# CTRL.net
KiCad netlist of a schematic drawn in EAGLE
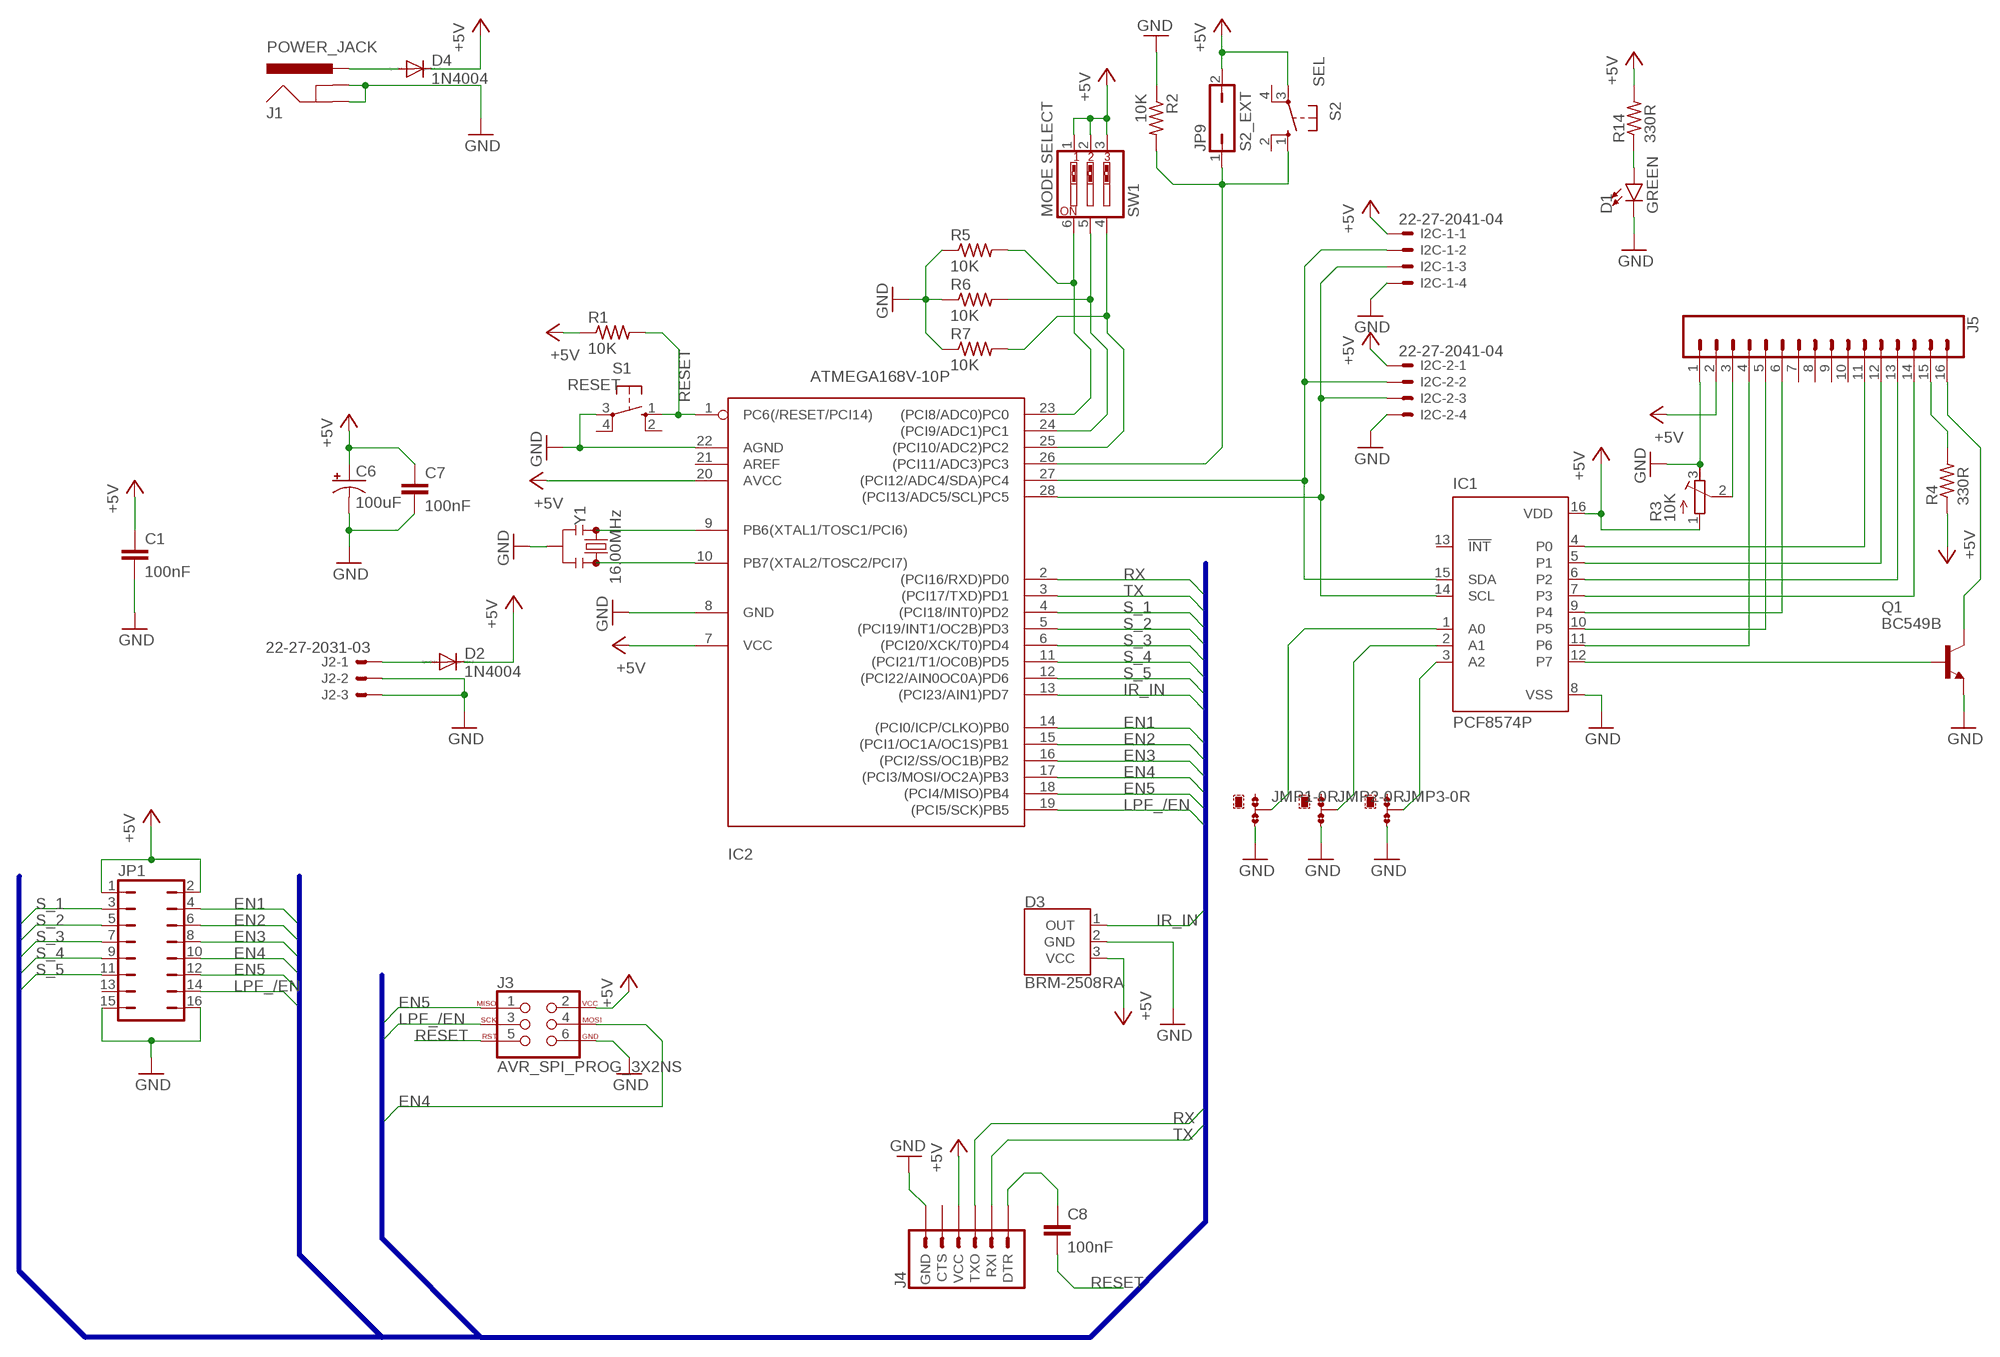
[diagram p0: schematic, sheet 1]

(export (version "E")
  (design (tool "Eeschema 10.0.6"))
  (components
    (comp (ref "C1")
      (value "100nF")
      (footprint "eagle-import:C075-032X103")
      (libsource (lib "eagle-import") (part "C-EU075-032X103"))
    )
    (comp (ref "C6")
      (value "100uF")
      (footprint "eagle-import:E2,5-7")
      (libsource (lib "eagle-import") (part "CPOL-USE2.5-7"))
    )
    (comp (ref "C7")
      (value "100nF")
      (footprint "eagle-import:C075-032X103")
      (libsource (lib "eagle-import") (part "C-EU075-032X103"))
    )
    (comp (ref "C8")
      (value "100nF")
      (footprint "eagle-import:C075-032X103")
      (libsource (lib "eagle-import") (part "C-EU075-032X103"))
    )
    (comp (ref "D1")
      (value "GREEN")
      (footprint "eagle-import:LED_5MM")
      (libsource (lib "eagle-import") (part "LED5MM"))
    )
    (comp (ref "D2")
      (value "1N4004")
      (footprint "eagle-import:DO41-10")
      (libsource (lib "eagle-import") (part "1N4004"))
    )
    (comp (ref "D3")
      (value "BRM-2508RA")
      (footprint "eagle-import:BRM-2508")
      (libsource (lib "eagle-import") (part "BRM-2508RA"))
    )
    (comp (ref "D4")
      (value "1N4004")
      (footprint "eagle-import:DO41-10")
      (libsource (lib "eagle-import") (part "1N4004"))
    )
    (comp (ref "I2C-1")
      (value "22-27-2041-04")
      (footprint "eagle-import:6410-04")
      (libsource (lib "eagle-import") (part "22-?-0427-2041"))
    )
    (comp (ref "I2C-2")
      (value "22-27-2041-04")
      (footprint "eagle-import:6410-04")
      (libsource (lib "eagle-import") (part "22-?-0427-2041"))
    )
    (comp (ref "IC1")
      (value "PCF8574P")
      (footprint "eagle-import:DIL16")
      (fields (field (name "MPN") "PCF8574PN"))
      (libsource (lib "eagle-import") (part "PCF8574P"))
    )
    (comp (ref "IC2")
      (value "ATMEGA168V-10P")
      (footprint "eagle-import:DIL28-3")
      (libsource (lib "eagle-import") (part "ATMEGA168PV-10"))
    )
    (comp (ref "J1")
      (value "POWER_JACK")
      (footprint "eagle-import:POWER_JACK_PTH")
      (libsource (lib "eagle-import") (part "POWER_JACK"))
    )
    (comp (ref "J2")
      (value "22-27-2031-03")
      (footprint "eagle-import:6410-03")
      (libsource (lib "eagle-import") (part "22-?-0327-2031"))
    )
    (comp (ref "J3")
      (value "AVR_SPI_PROG_3X2NS")
      (footprint "eagle-import:2X3-NS")
      (libsource (lib "eagle-import") (part "AVR_SPI_PROG_3X2NS"))
    )
    (comp (ref "J4")
      (value "6_PIN_SERIAL_TARGETSILK")
      (footprint "eagle-import:6_PIN_SERIAL_TARGET_SIDE_W_SILK")
      (libsource (lib "eagle-import") (part "6_PIN_SERIAL_TARGETSILK"))
    )
    (comp (ref "J5")
      (value "CONN_16LONGPADS")
      (footprint "eagle-import:1X16_LONGPADS")
      (libsource (lib "eagle-import") (part "CONN_16LONGPADS"))
    )
    (comp (ref "JMP1")
      (value "0R-JUMPB")
      (footprint "eagle-import:B0R-JMP")
      (libsource (lib "eagle-import") (part "0R-JUMPB"))
    )
    (comp (ref "JMP2")
      (value "0R-JUMPB")
      (footprint "eagle-import:B0R-JMP")
      (libsource (lib "eagle-import") (part "0R-JUMPB"))
    )
    (comp (ref "JMP3")
      (value "0R-JUMPB")
      (footprint "eagle-import:B0R-JMP")
      (libsource (lib "eagle-import") (part "0R-JUMPB"))
    )
    (comp (ref "JP1")
      (value "JP8Q")
      (footprint "eagle-import:JP8Q")
      (libsource (lib "eagle-import") (part "JP8Q"))
    )
    (comp (ref "JP9")
      (value "S2_EXT")
      (footprint "eagle-import:JP1")
      (libsource (lib "eagle-import") (part "JP1Q"))
    )
    (comp (ref "Q1")
      (value "BC549B")
      (footprint "eagle-import:TO92-EBC")
      (libsource (lib "eagle-import") (part "BC549B"))
    )
    (comp (ref "R1")
      (value "10K")
      (footprint "eagle-import:0204_7")
      (libsource (lib "eagle-import") (part "R-US_0204/7"))
    )
    (comp (ref "R2")
      (value "10K")
      (footprint "eagle-import:0204_7")
      (libsource (lib "eagle-import") (part "R-US_0204/7"))
    )
    (comp (ref "R3")
      (value "10K")
      (footprint "eagle-import:RTRIM3296P")
      (libsource (lib "eagle-import") (part "R-TRIMM3296P"))
    )
    (comp (ref "R4")
      (value "330R")
      (footprint "eagle-import:0204_7")
      (libsource (lib "eagle-import") (part "resistor_R-US_0204/7"))
    )
    (comp (ref "R5")
      (value "10K")
      (footprint "eagle-import:0204_7")
      (libsource (lib "eagle-import") (part "R-US_0204/7"))
    )
    (comp (ref "R6")
      (value "10K")
      (footprint "eagle-import:0204_7")
      (libsource (lib "eagle-import") (part "R-US_0204/7"))
    )
    (comp (ref "R7")
      (value "10K")
      (footprint "eagle-import:0204_7")
      (libsource (lib "eagle-import") (part "R-US_0204/7"))
    )
    (comp (ref "R14")
      (value "330R")
      (footprint "eagle-import:0204_7")
      (libsource (lib "eagle-import") (part "resistor_R-US_0204/7"))
    )
    (comp (ref "S1")
      (value "RESET")
      (footprint "eagle-import:B3F-10XX")
      (fields (field (name "MPN") "B3F-1000"))
      (libsource (lib "eagle-import") (part "10-XX"))
    )
    (comp (ref "S2")
      (value "SEL")
      (footprint "eagle-import:B3F-10XX")
      (fields (field (name "MPN") "B3F-1000"))
      (libsource (lib "eagle-import") (part "10-XX"))
    )
    (comp (ref "SW1")
      (value "MODE SELECT")
      (footprint "eagle-import:EDG-03")
      (libsource (lib "eagle-import") (part "SW_DIP-3"))
    )
    (comp (ref "Y1")
      (value "16.00MHz")
      (footprint "eagle-import:RESONATOR-PTH-7.6X3.8")
      (libsource (lib "eagle-import") (part "RESONATORPTH-7.6X3.8"))
    )
  )
  (nets
    (net (code "1") (name "+5V") (class "Default")
      (node (ref "C1") (pin "1") (pinfunction "1_1") (pintype "passive"))
      (node (ref "C6") (pin "+") (pinfunction "+_+") (pintype "passive"))
      (node (ref "C7") (pin "1") (pinfunction "1_1") (pintype "passive"))
      (node (ref "D2") (pin "C") (pinfunction "C_C") (pintype "passive"))
      (node (ref "D3") (pin "3") (pinfunction "VCC_3") (pintype "bidirectional"))
      (node (ref "D4") (pin "C") (pinfunction "C_C") (pintype "passive"))
      (node (ref "I2C-1") (pin "1") (pinfunction "S_1") (pintype "passive"))
      (node (ref "I2C-2") (pin "1") (pinfunction "S_1") (pintype "passive"))
      (node (ref "IC1") (pin "16") (pinfunction "VDD_16") (pintype "power_in"))
      (node (ref "IC2") (pin "20") (pinfunction "AVCC_20") (pintype "bidirectional"))
      (node (ref "IC2") (pin "7") (pinfunction "VCC_7") (pintype "bidirectional"))
      (node (ref "J3") (pin "2") (pinfunction "2_2") (pintype "passive"))
      (node (ref "J4") (pin "P$4") (pinfunction "VCC_P$4") (pintype "passive"))
      (node (ref "J5") (pin "2") (pinfunction "2_2") (pintype "passive"))
      (node (ref "JP1") (pin "1") (pinfunction "1_1") (pintype "passive"))
      (node (ref "JP1") (pin "2") (pinfunction "2_2") (pintype "passive"))
      (node (ref "JP9") (pin "2") (pinfunction "2_2") (pintype "passive"))
      (node (ref "R1") (pin "1") (pinfunction "1_1") (pintype "passive"))
      (node (ref "R14") (pin "2") (pinfunction "2_2") (pintype "passive"))
      (node (ref "R3") (pin "1") (pinfunction "A_1") (pintype "passive"))
      (node (ref "R4") (pin "1") (pinfunction "1_1") (pintype "passive"))
      (node (ref "S2") (pin "3") (pinfunction "P_3") (pintype "passive"))
      (node (ref "SW1") (pin "1") (pinfunction "1_1") (pintype "passive"))
      (node (ref "SW1") (pin "2") (pinfunction "2_2") (pintype "passive"))
      (node (ref "SW1") (pin "3") (pinfunction "3_3") (pintype "passive"))
    )
    (net (code "2") (name "/EN1") (class "Default")
      (node (ref "IC2") (pin "14") (pinfunction "(PCI0/ICP/CLKO)PB0_14") (pintype "bidirectional"))
      (node (ref "JP1") (pin "4") (pinfunction "4_4") (pintype "passive"))
    )
    (net (code "3") (name "/EN2") (class "Default")
      (node (ref "IC2") (pin "15") (pinfunction "(PCI1/OC1A/OC1S)PB1_15") (pintype "bidirectional"))
      (node (ref "JP1") (pin "6") (pinfunction "6_6") (pintype "passive"))
    )
    (net (code "4") (name "/EN3") (class "Default")
      (node (ref "IC2") (pin "16") (pinfunction "(PCI2/SS/OC1B)PB2_16") (pintype "bidirectional"))
      (node (ref "JP1") (pin "8") (pinfunction "8_8") (pintype "passive"))
    )
    (net (code "5") (name "/EN4") (class "Default")
      (node (ref "IC2") (pin "17") (pinfunction "(PCI3/MOSI/OC2A)PB3_17") (pintype "bidirectional"))
      (node (ref "J3") (pin "4") (pinfunction "4_4") (pintype "passive"))
      (node (ref "JP1") (pin "10") (pinfunction "10_10") (pintype "passive"))
    )
    (net (code "6") (name "/EN5") (class "Default")
      (node (ref "IC2") (pin "18") (pinfunction "(PCI4/MISO)PB4_18") (pintype "bidirectional"))
      (node (ref "J3") (pin "1") (pinfunction "1_1") (pintype "passive"))
      (node (ref "JP1") (pin "12") (pinfunction "12_12") (pintype "passive"))
    )
    (net (code "7") (name "/IR_IN") (class "Default")
      (node (ref "D3") (pin "1") (pinfunction "OUT_1") (pintype "bidirectional"))
      (node (ref "IC2") (pin "13") (pinfunction "(PCI23/AIN1)PD7_13") (pintype "bidirectional"))
    )
    (net (code "8") (name "/LPF_{slash}EN") (class "Default")
      (node (ref "IC2") (pin "19") (pinfunction "(PCI5/SCK)PB5_19") (pintype "bidirectional"))
      (node (ref "J3") (pin "3") (pinfunction "3_3") (pintype "passive"))
      (node (ref "JP1") (pin "14") (pinfunction "14_14") (pintype "passive"))
    )
    (net (code "9") (name "/RESET") (class "Default")
      (node (ref "C8") (pin "2") (pinfunction "2_2") (pintype "passive"))
      (node (ref "IC2") (pin "1") (pinfunction "PC6(/RESET/PCI14)_1") (pintype "bidirectional"))
      (node (ref "J3") (pin "5") (pinfunction "5_5") (pintype "passive"))
      (node (ref "R1") (pin "2") (pinfunction "2_2") (pintype "passive"))
      (node (ref "S1") (pin "1") (pinfunction "S_1") (pintype "passive"))
    )
    (net (code "10") (name "/RX") (class "Default")
      (node (ref "IC2") (pin "2") (pinfunction "(PCI16/RXD)PD0_2") (pintype "bidirectional"))
      (node (ref "J4") (pin "P$2") (pinfunction "TXO_P$2") (pintype "passive"))
    )
    (net (code "11") (name "/S_1") (class "Default")
      (node (ref "IC2") (pin "4") (pinfunction "(PCI18/INT0)PD2_4") (pintype "bidirectional"))
      (node (ref "JP1") (pin "3") (pinfunction "3_3") (pintype "passive"))
    )
    (net (code "12") (name "/S_2") (class "Default")
      (node (ref "IC2") (pin "5") (pinfunction "(PCI19/INT1/OC2B)PD3_5") (pintype "bidirectional"))
      (node (ref "JP1") (pin "5") (pinfunction "5_5") (pintype "passive"))
    )
    (net (code "13") (name "/S_3") (class "Default")
      (node (ref "IC2") (pin "6") (pinfunction "(PCI20/XCK/T0)PD4_6") (pintype "bidirectional"))
      (node (ref "JP1") (pin "7") (pinfunction "7_7") (pintype "passive"))
    )
    (net (code "14") (name "/S_4") (class "Default")
      (node (ref "IC2") (pin "11") (pinfunction "(PCI21/T1/OC0B)PD5_11") (pintype "bidirectional"))
      (node (ref "JP1") (pin "9") (pinfunction "9_9") (pintype "passive"))
    )
    (net (code "15") (name "/S_5") (class "Default")
      (node (ref "IC2") (pin "12") (pinfunction "(PCI22/AIN0OC0A)PD6_12") (pintype "bidirectional"))
      (node (ref "JP1") (pin "11") (pinfunction "11_11") (pintype "passive"))
    )
    (net (code "16") (name "/TX") (class "Default")
      (node (ref "IC2") (pin "3") (pinfunction "(PCI17/TXD)PD1_3") (pintype "bidirectional"))
      (node (ref "J4") (pin "P$3") (pinfunction "RXI_P$3") (pintype "passive"))
    )
    (net (code "17") (name "GND") (class "Default")
      (node (ref "C1") (pin "2") (pinfunction "2_2") (pintype "passive"))
      (node (ref "C6") (pin "-") (pinfunction "-_-") (pintype "passive"))
      (node (ref "C7") (pin "2") (pinfunction "2_2") (pintype "passive"))
      (node (ref "D1") (pin "K") (pinfunction "C_K") (pintype "passive"))
      (node (ref "D3") (pin "2") (pinfunction "GND_2") (pintype "bidirectional"))
      (node (ref "I2C-1") (pin "4") (pinfunction "S_4") (pintype "passive"))
      (node (ref "I2C-2") (pin "4") (pinfunction "S_4") (pintype "passive"))
      (node (ref "IC1") (pin "8") (pinfunction "VSS_8") (pintype "power_in"))
      (node (ref "IC2") (pin "22") (pinfunction "AGND_22") (pintype "bidirectional"))
      (node (ref "IC2") (pin "8") (pinfunction "GND_8") (pintype "bidirectional"))
      (node (ref "J1") (pin "GND") (pinfunction "GND_GND") (pintype "bidirectional"))
      (node (ref "J1") (pin "GNDBREAK") (pinfunction "GNDBREAK_GNDBREAK") (pintype "bidirectional"))
      (node (ref "J2") (pin "2") (pinfunction "S_2") (pintype "passive"))
      (node (ref "J2") (pin "3") (pinfunction "S_3") (pintype "passive"))
      (node (ref "J3") (pin "6") (pinfunction "6_6") (pintype "passive"))
      (node (ref "J4") (pin "P$6") (pinfunction "GND_P$6") (pintype "passive"))
      (node (ref "J5") (pin "1") (pinfunction "1_1") (pintype "passive"))
      (node (ref "JMP1") (pin "3") (pinfunction "3_3") (pintype "passive"))
      (node (ref "JMP2") (pin "3") (pinfunction "3_3") (pintype "passive"))
      (node (ref "JMP3") (pin "3") (pinfunction "3_3") (pintype "passive"))
      (node (ref "JP1") (pin "15") (pinfunction "15_15") (pintype "passive"))
      (node (ref "JP1") (pin "16") (pinfunction "16_16") (pintype "passive"))
      (node (ref "Q1") (pin "E") (pinfunction "E_E") (pintype "passive"))
      (node (ref "R2") (pin "1") (pinfunction "1_1") (pintype "passive"))
      (node (ref "R3") (pin "3") (pinfunction "E_3") (pintype "passive"))
      (node (ref "R5") (pin "1") (pinfunction "1_1") (pintype "passive"))
      (node (ref "R6") (pin "1") (pinfunction "1_1") (pintype "passive"))
      (node (ref "R7") (pin "1") (pinfunction "1_1") (pintype "passive"))
      (node (ref "S1") (pin "3") (pinfunction "P_3") (pintype "passive"))
      (node (ref "Y1") (pin "2") (pinfunction "2_2") (pintype "passive"))
    )
    (net (code "18") (name "Net-(D1-PadA)") (class "Default")
      (node (ref "D1") (pin "A") (pinfunction "A_A") (pintype "passive"))
      (node (ref "R14") (pin "1") (pinfunction "1_1") (pintype "passive"))
    )
    (net (code "19") (name "Net-(D4-PadA)") (class "Default")
      (node (ref "D4") (pin "A") (pinfunction "A_A") (pintype "passive"))
      (node (ref "J1") (pin "PWR") (pinfunction "PWR_PWR") (pintype "bidirectional"))
    )
    (net (code "20") (name "Net-(I2C-1B-S)") (class "Default")
      (node (ref "I2C-1") (pin "2") (pinfunction "S_2") (pintype "passive"))
      (node (ref "I2C-2") (pin "2") (pinfunction "S_2") (pintype "passive"))
      (node (ref "IC1") (pin "15") (pinfunction "SDA_15") (pintype "bidirectional"))
      (node (ref "IC2") (pin "27") (pinfunction "(PCI12/ADC4/SDA)PC4_27") (pintype "bidirectional"))
    )
    (net (code "21") (name "Net-(I2C-1C-S)") (class "Default")
      (node (ref "I2C-1") (pin "3") (pinfunction "S_3") (pintype "passive"))
      (node (ref "I2C-2") (pin "3") (pinfunction "S_3") (pintype "passive"))
      (node (ref "IC1") (pin "14") (pinfunction "SCL_14") (pintype "input"))
      (node (ref "IC2") (pin "28") (pinfunction "(PCI13/ADC5/SCL)PC5_28") (pintype "bidirectional"))
    )
    (net (code "22") (name "Net-(IC1-A0)") (class "Default")
      (node (ref "IC1") (pin "1") (pinfunction "A0_1") (pintype "input"))
      (node (ref "JMP1") (pin "2") (pinfunction "2_2") (pintype "passive"))
    )
    (net (code "23") (name "Net-(IC1-A1)") (class "Default")
      (node (ref "IC1") (pin "2") (pinfunction "A1_2") (pintype "input"))
      (node (ref "JMP2") (pin "2") (pinfunction "2_2") (pintype "passive"))
    )
    (net (code "24") (name "Net-(IC1-A2)") (class "Default")
      (node (ref "IC1") (pin "3") (pinfunction "A2_3") (pintype "input"))
      (node (ref "JMP3") (pin "2") (pinfunction "2_2") (pintype "passive"))
    )
    (net (code "25") (name "Net-(IC1-P0)") (class "Default")
      (node (ref "IC1") (pin "4") (pinfunction "P0_4") (pintype "bidirectional"))
      (node (ref "J5") (pin "11") (pinfunction "11_11") (pintype "passive"))
    )
    (net (code "26") (name "Net-(IC1-P1)") (class "Default")
      (node (ref "IC1") (pin "5") (pinfunction "P1_5") (pintype "bidirectional"))
      (node (ref "J5") (pin "12") (pinfunction "12_12") (pintype "passive"))
    )
    (net (code "27") (name "Net-(IC1-P2)") (class "Default")
      (node (ref "IC1") (pin "6") (pinfunction "P2_6") (pintype "bidirectional"))
      (node (ref "J5") (pin "13") (pinfunction "13_13") (pintype "passive"))
    )
    (net (code "28") (name "Net-(IC1-P3)") (class "Default")
      (node (ref "IC1") (pin "7") (pinfunction "P3_7") (pintype "bidirectional"))
      (node (ref "J5") (pin "14") (pinfunction "14_14") (pintype "passive"))
    )
    (net (code "29") (name "Net-(IC1-P4)") (class "Default")
      (node (ref "IC1") (pin "9") (pinfunction "P4_9") (pintype "bidirectional"))
      (node (ref "J5") (pin "6") (pinfunction "6_6") (pintype "passive"))
    )
    (net (code "30") (name "Net-(IC1-P5)") (class "Default")
      (node (ref "IC1") (pin "10") (pinfunction "P5_10") (pintype "bidirectional"))
      (node (ref "J5") (pin "5") (pinfunction "5_5") (pintype "passive"))
    )
    (net (code "31") (name "Net-(IC1-P6)") (class "Default")
      (node (ref "IC1") (pin "11") (pinfunction "P6_11") (pintype "bidirectional"))
      (node (ref "J5") (pin "4") (pinfunction "4_4") (pintype "passive"))
    )
    (net (code "32") (name "Net-(IC1-P7)") (class "Default")
      (node (ref "IC1") (pin "12") (pinfunction "P7_12") (pintype "bidirectional"))
      (node (ref "Q1") (pin "B") (pinfunction "B_B") (pintype "passive"))
    )
    (net (code "33") (name "Net-(IC2-(PCI8{slash}ADC0)PC0)") (class "Default")
      (node (ref "IC2") (pin "23") (pinfunction "(PCI8/ADC0)PC0_23") (pintype "bidirectional"))
      (node (ref "R5") (pin "2") (pinfunction "2_2") (pintype "passive"))
      (node (ref "SW1") (pin "6") (pinfunction "6_6") (pintype "passive"))
    )
    (net (code "34") (name "Net-(IC2-(PCI9{slash}ADC1)PC1)") (class "Default")
      (node (ref "IC2") (pin "24") (pinfunction "(PCI9/ADC1)PC1_24") (pintype "bidirectional"))
      (node (ref "R6") (pin "2") (pinfunction "2_2") (pintype "passive"))
      (node (ref "SW1") (pin "5") (pinfunction "5_5") (pintype "passive"))
    )
    (net (code "35") (name "Net-(IC2-(PCI10{slash}ADC2)PC2)") (class "Default")
      (node (ref "IC2") (pin "25") (pinfunction "(PCI10/ADC2)PC2_25") (pintype "bidirectional"))
      (node (ref "R7") (pin "2") (pinfunction "2_2") (pintype "passive"))
      (node (ref "SW1") (pin "4") (pinfunction "4_4") (pintype "passive"))
    )
    (net (code "36") (name "Net-(IC2-(PCI11{slash}ADC3)PC3)") (class "Default")
      (node (ref "IC2") (pin "26") (pinfunction "(PCI11/ADC3)PC3_26") (pintype "bidirectional"))
      (node (ref "JP9") (pin "1") (pinfunction "1_1") (pintype "passive"))
      (node (ref "R2") (pin "2") (pinfunction "2_2") (pintype "passive"))
      (node (ref "S2") (pin "1") (pinfunction "S_1") (pintype "passive"))
    )
    (net (code "37") (name "Net-(IC2-PB6(XTAL1{slash}TOSC1{slash}PCI6))") (class "Default")
      (node (ref "IC2") (pin "9") (pinfunction "PB6(XTAL1/TOSC1/PCI6)_9") (pintype "bidirectional"))
      (node (ref "Y1") (pin "1") (pinfunction "1_1") (pintype "passive"))
    )
    (net (code "38") (name "Net-(IC2-PB7(XTAL2{slash}TOSC2{slash}PCI7))") (class "Default")
      (node (ref "IC2") (pin "10") (pinfunction "PB7(XTAL2/TOSC2/PCI7)_10") (pintype "bidirectional"))
      (node (ref "Y1") (pin "3") (pinfunction "3_3") (pintype "passive"))
    )
    (net (code "39") (name "Net-(J2A-S)") (class "Default")
      (node (ref "D2") (pin "A") (pinfunction "A_A") (pintype "passive"))
      (node (ref "J2") (pin "1") (pinfunction "S_1") (pintype "passive"))
    )
    (net (code "40") (name "Net-(J4-DTR)") (class "Default")
      (node (ref "C8") (pin "1") (pinfunction "1_1") (pintype "passive"))
      (node (ref "J4") (pin "P$1") (pinfunction "DTR_P$1") (pintype "passive"))
    )
    (net (code "41") (name "Net-(J5-Pad15)") (class "Default")
      (node (ref "J5") (pin "15") (pinfunction "15_15") (pintype "passive"))
      (node (ref "R4") (pin "2") (pinfunction "2_2") (pintype "passive"))
    )
    (net (code "42") (name "Net-(J5-Pad16)") (class "Default")
      (node (ref "J5") (pin "16") (pinfunction "16_16") (pintype "passive"))
      (node (ref "Q1") (pin "C") (pinfunction "C_C") (pintype "passive"))
    )
    (net (code "43") (name "Net-(R3-S)") (class "Default")
      (node (ref "J5") (pin "3") (pinfunction "3_3") (pintype "passive"))
      (node (ref "R3") (pin "2") (pinfunction "S_2") (pintype "passive"))
    )
    (net (code "44") (name "unconnected-(IC1-~{INT}-Pad13)") (class "Default")
      (node (ref "IC1") (pin "13") (pinfunction "~{INT}_13") (pintype "output"))
    )
    (net (code "45") (name "unconnected-(IC2-AREF-Pad21)") (class "Default")
      (node (ref "IC2") (pin "21") (pinfunction "AREF_21") (pintype "bidirectional"))
    )
    (net (code "46") (name "unconnected-(J4-CTS-PadP$5)") (class "Default")
      (node (ref "J4") (pin "P$5") (pinfunction "CTS_P$5") (pintype "passive"))
    )
    (net (code "47") (name "unconnected-(J5-Pad7)") (class "Default")
      (node (ref "J5") (pin "7") (pinfunction "7_7") (pintype "passive"))
    )
    (net (code "48") (name "unconnected-(J5-Pad8)") (class "Default")
      (node (ref "J5") (pin "8") (pinfunction "8_8") (pintype "passive"))
    )
    (net (code "49") (name "unconnected-(J5-Pad9)") (class "Default")
      (node (ref "J5") (pin "9") (pinfunction "9_9") (pintype "passive"))
    )
    (net (code "50") (name "unconnected-(J5-Pad10)") (class "Default")
      (node (ref "J5") (pin "10") (pinfunction "10_10") (pintype "passive"))
    )
    (net (code "51") (name "unconnected-(JMP1-Pad1)") (class "Default")
      (node (ref "JMP1") (pin "1") (pinfunction "1_1") (pintype "passive"))
    )
    (net (code "52") (name "unconnected-(JMP2-Pad1)") (class "Default")
      (node (ref "JMP2") (pin "1") (pinfunction "1_1") (pintype "passive"))
    )
    (net (code "53") (name "unconnected-(JMP3-Pad1)") (class "Default")
      (node (ref "JMP3") (pin "1") (pinfunction "1_1") (pintype "passive"))
    )
    (net (code "54") (name "unconnected-(JP1-Pad13)") (class "Default")
      (node (ref "JP1") (pin "13") (pinfunction "13_13") (pintype "passive"))
    )
    (net (code "55") (name "unconnected-(S1-P1-Pad4)") (class "Default")
      (node (ref "S1") (pin "4") (pinfunction "P1_4") (pintype "passive"))
    )
    (net (code "56") (name "unconnected-(S1-S1-Pad2)") (class "Default")
      (node (ref "S1") (pin "2") (pinfunction "S1_2") (pintype "passive"))
    )
    (net (code "57") (name "unconnected-(S2-P1-Pad4)") (class "Default")
      (node (ref "S2") (pin "4") (pinfunction "P1_4") (pintype "passive"))
    )
    (net (code "58") (name "unconnected-(S2-S1-Pad2)") (class "Default")
      (node (ref "S2") (pin "2") (pinfunction "S1_2") (pintype "passive"))
    )
  )
)
